# TemSensor_CON.net
KiCad netlist of a schematic drawn in Altium Designer
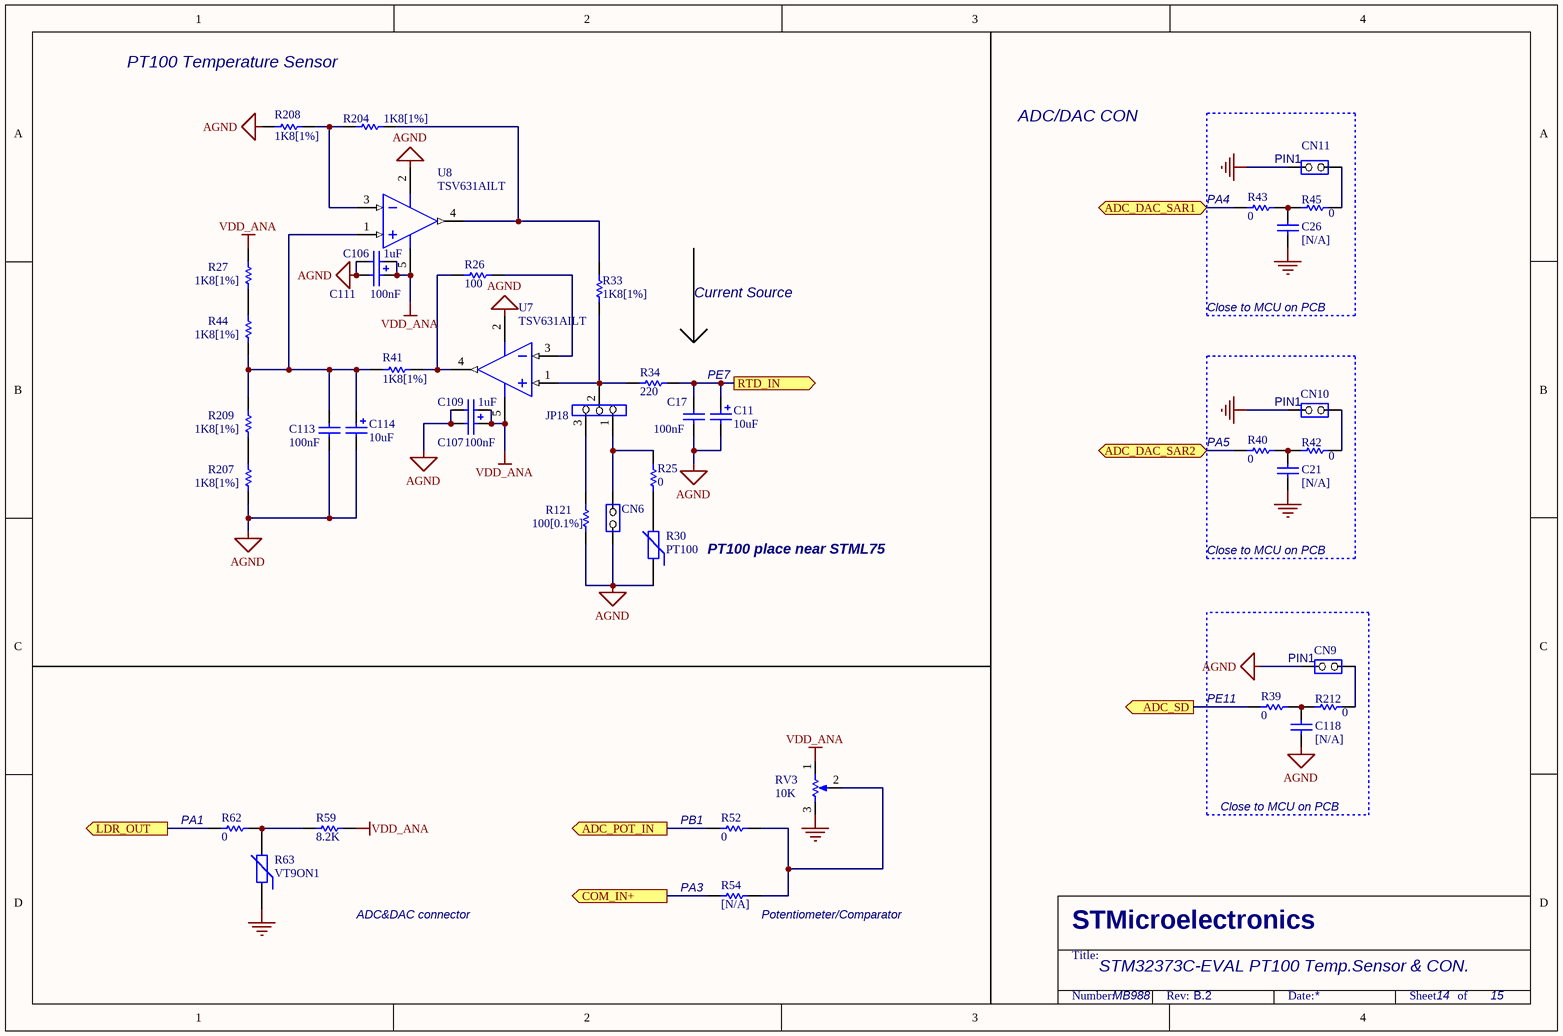
[diagram p0: TemSensor&CON.SchDoc]

(export (version "E")
  (design (tool "Eeschema 10.0.6"))
  (components
    (comp (ref "C11")
      (value "10uF")
      (footprint "TAN-A")
      (description "Polarized Capacitor (Radial)")
      (fields (field (name "PUBLISHER") "Altium Limited"))
      (libsource (lib "Miscellaneous Devices") (part "Cap Pol1"))
    )
    (comp (ref "C17")
      (value "100nF")
      (footprint "0603C")
      (description "Capacitor")
      (fields (field (name "PUBLISHER") "Altium Limited"))
      (libsource (lib "Miscellaneous Devices") (part "CAP"))
    )
    (comp (ref "C21")
      (value "[N/A]")
      (footprint "0603C")
      (description "Capacitor")
      (fields (field (name "PUBLISHER") "Altium Limited"))
      (libsource (lib "Miscellaneous Devices") (part "cap"))
    )
    (comp (ref "C26")
      (value "[N/A]")
      (footprint "0603C")
      (description "Capacitor")
      (fields (field (name "PUBLISHER") "Altium Limited"))
      (libsource (lib "Miscellaneous Devices") (part "cap"))
    )
    (comp (ref "C106")
      (value "1uF")
      (footprint "TAN-A")
      (description "Polarized Capacitor (Radial)")
      (fields (field (name "PUBLISHER") "Altium Limited"))
      (libsource (lib "Miscellaneous Devices") (part "Cap Pol1"))
    )
    (comp (ref "C107")
      (value "100nF")
      (footprint "0603C")
      (description "Capacitor")
      (fields (field (name "PUBLISHER") "Altium Limited"))
      (libsource (lib "Miscellaneous Devices") (part "CAP"))
    )
    (comp (ref "C109")
      (value "1uF")
      (footprint "TAN-A")
      (description "Polarized Capacitor (Radial)")
      (fields (field (name "PUBLISHER") "Altium Limited"))
      (libsource (lib "Miscellaneous Devices") (part "Cap Pol1"))
    )
    (comp (ref "C111")
      (value "100nF")
      (footprint "0603C")
      (description "Capacitor")
      (fields (field (name "PUBLISHER") "Altium Limited"))
      (libsource (lib "Miscellaneous Devices") (part "CAP"))
    )
    (comp (ref "C113")
      (value "100nF")
      (footprint "0603C")
      (description "Capacitor")
      (fields (field (name "PUBLISHER") "Altium Limited"))
      (libsource (lib "Miscellaneous Devices") (part "CAP"))
    )
    (comp (ref "C114")
      (value "10uF")
      (footprint "TAN-A")
      (description "Polarized Capacitor (Radial)")
      (fields (field (name "PUBLISHER") "Altium Limited"))
      (libsource (lib "Miscellaneous Devices") (part "Cap Pol1"))
    )
    (comp (ref "C118")
      (value "[N/A]")
      (footprint "0603C")
      (description "Capacitor")
      (fields (field (name "PUBLISHER") "Altium Limited"))
      (libsource (lib "Miscellaneous Devices") (part "cap"))
    )
    (comp (ref "CN6") (value "~") (footprint "SIP2") (libsource (lib "*") (part "JP2")))
    (comp (ref "CN9") (value "~") (footprint "SIP2") (libsource (lib "*") (part "JP2")))
    (comp (ref "CN10") (value "~") (footprint "SIP2") (libsource (lib "*") (part "JP2")))
    (comp (ref "CN11") (value "~") (footprint "SIP2") (libsource (lib "*") (part "JP2")))
    (comp (ref "JP18") (value "~") (footprint "SIP3") (libsource (lib "STR910_SCHLIB") (part "Jumper3")))
    (comp (ref "R25")
      (value "0")
      (footprint "0603R")
      (description "Resistor")
      (fields (field (name "PUBLISHER") "Altium Limited"))
      (libsource (lib "Miscellaneous Devices") (part "Res1"))
    )
    (comp (ref "R26")
      (value "100")
      (footprint "0603R")
      (description "Resistor")
      (fields (field (name "PUBLISHER") "Altium Limited"))
      (libsource (lib "Miscellaneous Devices") (part "Res1"))
    )
    (comp (ref "R27")
      (value "1K8[1%]")
      (footprint "0603R")
      (description "Resistor")
      (fields (field (name "PUBLISHER") "Altium Limited"))
      (libsource (lib "Miscellaneous Devices") (part "Res1"))
    )
    (comp (ref "R30")
      (value "PT100")
      (footprint "0805R")
      (description "Varistor (Voltage-Sensitive Resistor)")
      (fields (field (name "PUBLISHER") "Altium Limited"))
      (libsource (lib "MB988") (part "PT100"))
    )
    (comp (ref "R33")
      (value "1K8[1%]")
      (footprint "0603R")
      (description "Resistor")
      (fields (field (name "PUBLISHER") "Altium Limited"))
      (libsource (lib "Miscellaneous Devices") (part "Res1"))
    )
    (comp (ref "R34")
      (value "220")
      (footprint "0603R")
      (description "Resistor")
      (fields (field (name "PUBLISHER") "Altium Limited"))
      (libsource (lib "Miscellaneous Devices") (part "Res1"))
    )
    (comp (ref "R39")
      (value "0")
      (footprint "0603R")
      (description "Resistor")
      (fields (field (name "PUBLISHER") "Altium Limited"))
      (libsource (lib "Miscellaneous Devices") (part "Res1"))
    )
    (comp (ref "R40")
      (value "0")
      (footprint "0603R")
      (description "Resistor")
      (fields (field (name "PUBLISHER") "Altium Limited"))
      (libsource (lib "Miscellaneous Devices") (part "Res1"))
    )
    (comp (ref "R41")
      (value "1K8[1%]")
      (footprint "0603R")
      (description "Resistor")
      (fields (field (name "PUBLISHER") "Altium Limited"))
      (libsource (lib "Miscellaneous Devices") (part "Res1"))
    )
    (comp (ref "R42")
      (value "0")
      (footprint "0603R")
      (description "Resistor")
      (fields (field (name "PUBLISHER") "Altium Limited"))
      (libsource (lib "Miscellaneous Devices") (part "Res1"))
    )
    (comp (ref "R43")
      (value "0")
      (footprint "0603R")
      (description "Resistor")
      (fields (field (name "PUBLISHER") "Altium Limited"))
      (libsource (lib "Miscellaneous Devices") (part "Res1"))
    )
    (comp (ref "R44")
      (value "1K8[1%]")
      (footprint "0603R")
      (description "Resistor")
      (fields (field (name "PUBLISHER") "Altium Limited"))
      (libsource (lib "Miscellaneous Devices") (part "Res1"))
    )
    (comp (ref "R45")
      (value "0")
      (footprint "0603R")
      (description "Resistor")
      (fields (field (name "PUBLISHER") "Altium Limited"))
      (libsource (lib "Miscellaneous Devices") (part "Res1"))
    )
    (comp (ref "R52")
      (value "0")
      (footprint "0603R")
      (description "Resistor")
      (fields (field (name "PUBLISHER") "Altium Limited"))
      (libsource (lib "Miscellaneous Devices") (part "Res1"))
    )
    (comp (ref "R54")
      (value "[N/A]")
      (footprint "0603R")
      (description "Resistor")
      (fields (field (name "PUBLISHER") "Altium Limited"))
      (libsource (lib "Miscellaneous Devices") (part "Res1"))
    )
    (comp (ref "R59")
      (value "8.2K")
      (footprint "0603R")
      (description "Resistor")
      (fields (field (name "PUBLISHER") "Altium Limited"))
      (libsource (lib "Miscellaneous Devices") (part "Res1"))
    )
    (comp (ref "R62")
      (value "0")
      (footprint "0603R")
      (description "Resistor")
      (fields (field (name "PUBLISHER") "Altium Limited"))
      (libsource (lib "Miscellaneous Devices") (part "Res1"))
    )
    (comp (ref "R63")
      (value "VT9ON1")
      (footprint "PVT901")
      (description "Varistor (Voltage-Sensitive Resistor)")
      (fields (field (name "PUBLISHER") "Altium Limited"))
      (libsource (lib "Miscellaneous Devices") (part "Res Varistor"))
    )
    (comp (ref "R121")
      (value "100[0.1%]")
      (footprint "0603R")
      (description "Resistor")
      (fields (field (name "PUBLISHER") "Altium Limited"))
      (libsource (lib "Miscellaneous Devices") (part "Res1"))
    )
    (comp (ref "R204")
      (value "1K8[1%]")
      (footprint "0603R")
      (description "Resistor")
      (fields (field (name "PUBLISHER") "Altium Limited"))
      (libsource (lib "Miscellaneous Devices") (part "Res1"))
    )
    (comp (ref "R207")
      (value "1K8[1%]")
      (footprint "0603R")
      (description "Resistor")
      (fields (field (name "PUBLISHER") "Altium Limited"))
      (libsource (lib "Miscellaneous Devices") (part "Res1"))
    )
    (comp (ref "R208")
      (value "1K8[1%]")
      (footprint "0603R")
      (description "Resistor")
      (fields (field (name "PUBLISHER") "Altium Limited"))
      (libsource (lib "Miscellaneous Devices") (part "Res1"))
    )
    (comp (ref "R209")
      (value "1K8[1%]")
      (footprint "0603R")
      (description "Resistor")
      (fields (field (name "PUBLISHER") "Altium Limited"))
      (libsource (lib "Miscellaneous Devices") (part "Res1"))
    )
    (comp (ref "R212")
      (value "0")
      (footprint "0603R")
      (description "Resistor")
      (fields (field (name "PUBLISHER") "Altium Limited"))
      (libsource (lib "Miscellaneous Devices") (part "Res1"))
    )
    (comp (ref "RV3") (value "10K") (footprint "3296W") (libsource (lib "STR910_SCHLIB") (part "RV")))
    (comp (ref "U7")
      (value "TSV631AILT")
      (footprint "SOT-23-5L")
      (libsource (lib "MB988") (part "TSV631AILT"))
    )
    (comp (ref "U8")
      (value "TSV631AILT")
      (footprint "SOT-23-5L")
      (libsource (lib "MB988") (part "TSV631AILT"))
    )
  )
  (nets
    (net (code "1") (name "/ADC_DAC_SAR1") (class "Default")
      (node (ref "R43") (pin "1") (pinfunction "1_1") (pintype "passive"))
    )
    (net (code "2") (name "/ADC_DAC_SAR2") (class "Default")
      (node (ref "R40") (pin "1") (pinfunction "1_1") (pintype "passive"))
    )
    (net (code "3") (name "/ADC_POT_IN") (class "Default")
      (node (ref "R52") (pin "1") (pinfunction "1_1") (pintype "passive"))
    )
    (net (code "4") (name "/ADC_SD") (class "Default")
      (node (ref "R39") (pin "1") (pinfunction "1_1") (pintype "passive"))
    )
    (net (code "5") (name "/COM_IN+") (class "Default")
      (node (ref "R54") (pin "1") (pinfunction "1_1") (pintype "passive"))
    )
    (net (code "6") (name "/LDR_OUT") (class "Default")
      (node (ref "R62") (pin "2") (pinfunction "2_2") (pintype "passive"))
    )
    (net (code "7") (name "/RTD_IN") (class "Default")
      (node (ref "C11") (pin "1") (pinfunction "1_1") (pintype "passive"))
      (node (ref "C17") (pin "2") (pinfunction "2_2") (pintype "passive"))
      (node (ref "R34") (pin "1") (pinfunction "1_1") (pintype "passive"))
    )
    (net (code "8") (name "AGND") (class "Default")
      (node (ref "C106") (pin "2") (pinfunction "2_2") (pintype "passive"))
      (node (ref "C107") (pin "1") (pinfunction "1_1") (pintype "passive"))
      (node (ref "C109") (pin "2") (pinfunction "2_2") (pintype "passive"))
      (node (ref "C11") (pin "2") (pinfunction "2_2") (pintype "passive"))
      (node (ref "C111") (pin "1") (pinfunction "1_1") (pintype "passive"))
      (node (ref "C113") (pin "1") (pinfunction "1_1") (pintype "passive"))
      (node (ref "C114") (pin "2") (pinfunction "2_2") (pintype "passive"))
      (node (ref "C118") (pin "1") (pinfunction "1_1") (pintype "passive"))
      (node (ref "C17") (pin "1") (pinfunction "1_1") (pintype "passive"))
      (node (ref "CN6") (pin "2") (pinfunction "NO_2") (pintype "passive"))
      (node (ref "CN9") (pin "1") (pinfunction "COMMON_1") (pintype "passive"))
      (node (ref "R121") (pin "2") (pinfunction "2_2") (pintype "passive"))
      (node (ref "R207") (pin "2") (pinfunction "2_2") (pintype "passive"))
      (node (ref "R208") (pin "1") (pinfunction "1_1") (pintype "passive"))
      (node (ref "R30") (pin "1") (pinfunction "1_1") (pintype "passive"))
      (node (ref "U7") (pin "2") (pinfunction "VDD_2") (pintype "power_in"))
      (node (ref "U8") (pin "2") (pinfunction "VDD_2") (pintype "power_in"))
    )
    (net (code "9") (name "GND") (class "Default")
      (node (ref "C21") (pin "1") (pinfunction "1_1") (pintype "passive"))
      (node (ref "C26") (pin "1") (pinfunction "1_1") (pintype "passive"))
      (node (ref "CN10") (pin "1") (pinfunction "COMMON_1") (pintype "passive"))
      (node (ref "CN11") (pin "1") (pinfunction "COMMON_1") (pintype "passive"))
      (node (ref "R63") (pin "1") (pinfunction "1_1") (pintype "passive"))
      (node (ref "RV3") (pin "3") (pinfunction "TOP_3") (pintype "passive"))
    )
    (net (code "10") (name "Net-(C21-Pad2)") (class "Default")
      (node (ref "C21") (pin "2") (pinfunction "2_2") (pintype "passive"))
      (node (ref "R40") (pin "2") (pinfunction "2_2") (pintype "passive"))
      (node (ref "R42") (pin "1") (pinfunction "1_1") (pintype "passive"))
    )
    (net (code "11") (name "Net-(C26-Pad2)") (class "Default")
      (node (ref "C26") (pin "2") (pinfunction "2_2") (pintype "passive"))
      (node (ref "R43") (pin "2") (pinfunction "2_2") (pintype "passive"))
      (node (ref "R45") (pin "1") (pinfunction "1_1") (pintype "passive"))
    )
    (net (code "12") (name "Net-(C118-Pad2)") (class "Default")
      (node (ref "C118") (pin "2") (pinfunction "2_2") (pintype "passive"))
      (node (ref "R212") (pin "1") (pinfunction "1_1") (pintype "passive"))
      (node (ref "R39") (pin "2") (pinfunction "2_2") (pintype "passive"))
    )
    (net (code "13") (name "Net-(CN6-COMMON)") (class "Default")
      (node (ref "CN6") (pin "1") (pinfunction "COMMON_1") (pintype "passive"))
      (node (ref "JP18") (pin "1") (pintype "passive"))
      (node (ref "R25") (pin "1") (pinfunction "1_1") (pintype "passive"))
    )
    (net (code "14") (name "Net-(CN9-NO)") (class "Default")
      (node (ref "CN9") (pin "2") (pinfunction "NO_2") (pintype "passive"))
      (node (ref "R212") (pin "2") (pinfunction "2_2") (pintype "passive"))
    )
    (net (code "15") (name "Net-(CN10-NO)") (class "Default")
      (node (ref "CN10") (pin "2") (pinfunction "NO_2") (pintype "passive"))
      (node (ref "R42") (pin "2") (pinfunction "2_2") (pintype "passive"))
    )
    (net (code "16") (name "Net-(CN11-NO)") (class "Default")
      (node (ref "CN11") (pin "2") (pinfunction "NO_2") (pintype "passive"))
      (node (ref "R45") (pin "2") (pinfunction "2_2") (pintype "passive"))
    )
    (net (code "17") (name "Net-(JP18-Pad3)") (class "Default")
      (node (ref "JP18") (pin "3") (pintype "passive"))
      (node (ref "R121") (pin "1") (pinfunction "1_1") (pintype "passive"))
    )
    (net (code "18") (name "Net-(R25-Pad2)") (class "Default")
      (node (ref "R25") (pin "2") (pinfunction "2_2") (pintype "passive"))
      (node (ref "R30") (pin "2") (pinfunction "2_2") (pintype "passive"))
    )
    (net (code "19") (name "Net-(R27-Pad2)") (class "Default")
      (node (ref "R27") (pin "2") (pinfunction "2_2") (pintype "passive"))
      (node (ref "R44") (pin "1") (pinfunction "1_1") (pintype "passive"))
    )
    (net (code "20") (name "Net-(R59-Pad1)") (class "Default")
      (node (ref "R59") (pin "1") (pinfunction "1_1") (pintype "passive"))
      (node (ref "R62") (pin "1") (pinfunction "1_1") (pintype "passive"))
      (node (ref "R63") (pin "2") (pinfunction "2_2") (pintype "passive"))
    )
    (net (code "21") (name "Net-(R207-Pad1)") (class "Default")
      (node (ref "R207") (pin "1") (pinfunction "1_1") (pintype "passive"))
      (node (ref "R209") (pin "2") (pinfunction "2_2") (pintype "passive"))
    )
    (net (code "22") (name "Net-(RV3-TAP)") (class "Default")
      (node (ref "R52") (pin "2") (pinfunction "2_2") (pintype "passive"))
      (node (ref "R54") (pin "2") (pinfunction "2_2") (pintype "passive"))
      (node (ref "RV3") (pin "2") (pinfunction "TAP_2") (pintype "passive"))
    )
    (net (code "23") (name "Net-(U7-IN+)") (class "Default")
      (node (ref "JP18") (pin "2") (pintype "passive"))
      (node (ref "R33") (pin "2") (pinfunction "2_2") (pintype "passive"))
      (node (ref "R34") (pin "2") (pinfunction "2_2") (pintype "passive"))
      (node (ref "U7") (pin "1") (pinfunction "IN+_1") (pintype "input"))
    )
    (net (code "24") (name "Net-(U7-IN-)") (class "Default")
      (node (ref "R26") (pin "1") (pinfunction "1_1") (pintype "passive"))
      (node (ref "U7") (pin "3") (pinfunction "IN-_3") (pintype "input"))
    )
    (net (code "25") (name "Net-(U7-OUT)") (class "Default")
      (node (ref "R26") (pin "2") (pinfunction "2_2") (pintype "passive"))
      (node (ref "R41") (pin "2") (pinfunction "2_2") (pintype "passive"))
      (node (ref "U7") (pin "4") (pinfunction "OUT_4") (pintype "output"))
    )
    (net (code "26") (name "Net-(U8-IN+)") (class "Default")
      (node (ref "C113") (pin "2") (pinfunction "2_2") (pintype "passive"))
      (node (ref "C114") (pin "1") (pinfunction "1_1") (pintype "passive"))
      (node (ref "R209") (pin "1") (pinfunction "1_1") (pintype "passive"))
      (node (ref "R41") (pin "1") (pinfunction "1_1") (pintype "passive"))
      (node (ref "R44") (pin "2") (pinfunction "2_2") (pintype "passive"))
      (node (ref "U8") (pin "1") (pinfunction "IN+_1") (pintype "input"))
    )
    (net (code "27") (name "Net-(U8-IN-)") (class "Default")
      (node (ref "R204") (pin "1") (pinfunction "1_1") (pintype "passive"))
      (node (ref "R208") (pin "2") (pinfunction "2_2") (pintype "passive"))
      (node (ref "U8") (pin "3") (pinfunction "IN-_3") (pintype "input"))
    )
    (net (code "28") (name "Net-(U8-OUT)") (class "Default")
      (node (ref "R204") (pin "2") (pinfunction "2_2") (pintype "passive"))
      (node (ref "R33") (pin "1") (pinfunction "1_1") (pintype "passive"))
      (node (ref "U8") (pin "4") (pinfunction "OUT_4") (pintype "output"))
    )
    (net (code "29") (name "VDD_ANA") (class "Default")
      (node (ref "C106") (pin "1") (pinfunction "1_1") (pintype "passive"))
      (node (ref "C107") (pin "2") (pinfunction "2_2") (pintype "passive"))
      (node (ref "C109") (pin "1") (pinfunction "1_1") (pintype "passive"))
      (node (ref "C111") (pin "2") (pinfunction "2_2") (pintype "passive"))
      (node (ref "R27") (pin "1") (pinfunction "1_1") (pintype "passive"))
      (node (ref "R59") (pin "2") (pinfunction "2_2") (pintype "passive"))
      (node (ref "RV3") (pin "1") (pinfunction "BOT_1") (pintype "passive"))
      (node (ref "U7") (pin "5") (pinfunction "VCC_5") (pintype "power_in"))
      (node (ref "U8") (pin "5") (pinfunction "VCC_5") (pintype "power_in"))
    )
  )
)
